# os32_master.net
KiCad netlist of a schematic drawn in EAGLE
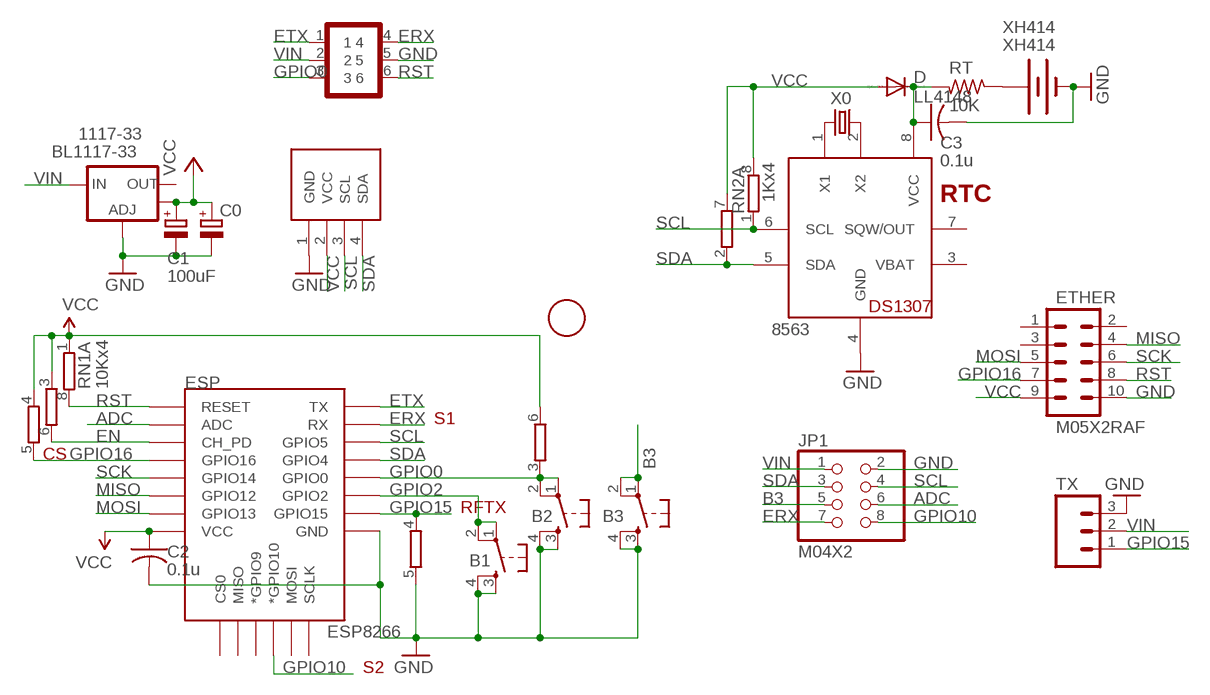
[diagram p0: schematic, sheet 1]

(export (version "E")
  (design (tool "Eeschema 10.0.6"))
  (components
    (comp (ref "1F")
      (value "FIDUCIAL")
      (footprint "eagle-import:FIDUCIAL_1MM")
      (libsource (lib "eagle-import") (part "FIDUCIAL"))
    )
    (comp (ref "1117-33")
      (value "BL1117-33")
      (footprint "eagle-import:SOT223")
      (libsource (lib "eagle-import") (part "V_REG_LM1117SOT223"))
    )
    (comp (ref "8563")
      (value "PCF8563")
      (footprint "eagle-import:SO08")
      (libsource (lib "eagle-import") (part "DS1307SOIC"))
    )
    (comp (ref "B1")
      (value "SPST_TACTEVQQ2")
      (footprint "eagle-import:EVQ-Q2")
      (libsource (lib "eagle-import") (part "SPST_TACTEVQQ2"))
    )
    (comp (ref "B2")
      (value "SPST_TACTEVQQ2")
      (footprint "eagle-import:EVQ-Q2")
      (libsource (lib "eagle-import") (part "SPST_TACTEVQQ2"))
    )
    (comp (ref "B3")
      (value "SPST_TACTEVQQ2")
      (footprint "eagle-import:EVQ-Q2")
      (libsource (lib "eagle-import") (part "SPST_TACTEVQQ2"))
    )
    (comp (ref "C0")
      (value "CPOL-EUE2.5-5")
      (footprint "eagle-import:E2,5-5")
      (libsource (lib "eagle-import") (part "CPOL-EUE2.5-5"))
    )
    (comp (ref "C1")
      (value "100uF")
      (footprint "eagle-import:CT3528")
      (libsource (lib "eagle-import") (part "resistor_CPOL-EUCT3528"))
    )
    (comp (ref "C2")
      (value "0.1u")
      (footprint "eagle-import:C0603")
      (libsource (lib "eagle-import") (part "C-USC0603"))
    )
    (comp (ref "C3")
      (value "0.1u")
      (footprint "eagle-import:C0603")
      (libsource (lib "eagle-import") (part "C-USC0603"))
    )
    (comp (ref "D")
      (value "LL4148")
      (footprint "eagle-import:MINIMELF")
      (libsource (lib "eagle-import") (part "DIODE-MINIMELF"))
    )
    (comp (ref "ESP")
      (value "ESP8266")
      (footprint "eagle-import:ESP12E-SMD")
      (libsource (lib "eagle-import") (part "ESP12ESMD"))
    )
    (comp (ref "ETHER")
      (value "M05X2RAF")
      (footprint "eagle-import:2X5-RAF")
      (libsource (lib "eagle-import") (part "M05X2RAF"))
    )
    (comp (ref "JP1")
      (value "M04X2")
      (footprint "eagle-import:2X04")
      (libsource (lib "eagle-import") (part "PINHD-2X4"))
    )
    (comp (ref "LCD")
      (value "SSD1306_OLED_I2CSMD3")
      (footprint "eagle-import:SSD1306_OLED_I2C_SMD3")
      (libsource (lib "eagle-import") (part "SSD1306_OLED_I2CSMD3"))
    )
    (comp (ref "RN1")
      (value "10Kx4")
      (footprint "eagle-import:EXB38V")
      (libsource (lib "eagle-import") (part "4R-NEXB38V"))
    )
    (comp (ref "RN2")
      (value "1Kx4")
      (footprint "eagle-import:EXB38V")
      (libsource (lib "eagle-import") (part "4R-NEXB38V"))
    )
    (comp (ref "RT")
      (value "10K")
      (footprint "eagle-import:R0603")
      (libsource (lib "eagle-import") (part "R-US_R0603"))
    )
    (comp (ref "TX")
      (value "M03LOCK")
      (footprint "eagle-import:1X03_LOCK")
      (libsource (lib "eagle-import") (part "M03LOCK"))
    )
    (comp (ref "U$3")
      (value "GOLDFINGER_2X3")
      (footprint "eagle-import:GOLDFINGER_2X3")
      (libsource (lib "eagle-import") (part "GOLDFINGER_2X3"))
    )
    (comp (ref "X0")
      (value "32.768kHz")
      (footprint "eagle-import:MM20SS1")
      (libsource (lib "eagle-import") (part "CRYSTALMM20SS1"))
    )
    (comp (ref "XH414")
      (value "XH414")
      (footprint "eagle-import:BATTCON_XH414")
      (libsource (lib "eagle-import") (part "BATTERYXH414"))
    )
  )
  (nets
    (net (code "1") (name "/ADC") (class "Default")
      (node (ref "ESP") (pin "ADC") (pinfunction "ADC_ADC") (pintype "bidirectional"))
      (node (ref "JP1") (pin "6") (pinfunction "6_6") (pintype "passive"))
    )
    (net (code "2") (name "/B3") (class "Default")
      (node (ref "B3") (pin "1") (pinfunction "1_1") (pintype "passive"))
      (node (ref "B3") (pin "2") (pinfunction "2_2") (pintype "passive"))
      (node (ref "JP1") (pin "5") (pinfunction "5_5") (pintype "passive"))
    )
    (net (code "3") (name "/EN") (class "Default")
      (node (ref "ESP") (pin "CH_PD") (pinfunction "CH_PD_CH_PD") (pintype "bidirectional"))
      (node (ref "RN1") (pin "6") (pinfunction "2_6") (pintype "passive"))
    )
    (net (code "4") (name "/ERX") (class "Default")
      (node (ref "ESP") (pin "RXD0") (pinfunction "RX_RXD0") (pintype "bidirectional"))
      (node (ref "JP1") (pin "7") (pinfunction "7_7") (pintype "passive"))
      (node (ref "U$3") (pin "4") (pinfunction "4_4") (pintype "bidirectional"))
    )
    (net (code "5") (name "/ETX") (class "Default")
      (node (ref "ESP") (pin "TXD0") (pinfunction "TX_TXD0") (pintype "bidirectional"))
      (node (ref "U$3") (pin "1") (pinfunction "1_1") (pintype "bidirectional"))
    )
    (net (code "6") (name "/GPIO0") (class "Default")
      (node (ref "B2") (pin "1") (pinfunction "1_1") (pintype "passive"))
      (node (ref "B2") (pin "2") (pinfunction "2_2") (pintype "passive"))
      (node (ref "ESP") (pin "GPIO0") (pinfunction "GPIO0_GPIO0") (pintype "bidirectional"))
      (node (ref "RN2") (pin "3") (pinfunction "1_3") (pintype "passive"))
      (node (ref "U$3") (pin "3") (pinfunction "3_3") (pintype "bidirectional"))
    )
    (net (code "7") (name "/GPIO2") (class "Default")
      (node (ref "B1") (pin "1") (pinfunction "1_1") (pintype "passive"))
      (node (ref "B1") (pin "2") (pinfunction "2_2") (pintype "passive"))
      (node (ref "ESP") (pin "GPIO2") (pinfunction "GPIO2_GPIO2") (pintype "bidirectional"))
    )
    (net (code "8") (name "/GPIO10") (class "Default")
      (node (ref "ESP") (pin "GPIO10") (pinfunction "*GPIO10_GPIO10") (pintype "bidirectional"))
      (node (ref "JP1") (pin "8") (pinfunction "8_8") (pintype "passive"))
    )
    (net (code "9") (name "/GPIO15") (class "Default")
      (node (ref "ESP") (pin "GPIO15") (pinfunction "GPIO15_GPIO15") (pintype "bidirectional"))
      (node (ref "RN2") (pin "4") (pinfunction "1_4") (pintype "passive"))
      (node (ref "TX") (pin "1") (pinfunction "1_1") (pintype "passive"))
    )
    (net (code "10") (name "/GPIO16") (class "Default")
      (node (ref "ESP") (pin "GPIO16") (pinfunction "GPIO16_GPIO16") (pintype "bidirectional"))
      (node (ref "ETHER") (pin "7") (pinfunction "7_7") (pintype "passive"))
      (node (ref "RN1") (pin "5") (pinfunction "2_5") (pintype "passive"))
    )
    (net (code "11") (name "/MISO") (class "Default")
      (node (ref "ESP") (pin "GPIO12") (pinfunction "GPIO12_GPIO12") (pintype "bidirectional"))
      (node (ref "ETHER") (pin "4") (pinfunction "4_4") (pintype "passive"))
    )
    (net (code "12") (name "/MOSI") (class "Default")
      (node (ref "ESP") (pin "GPIO13") (pinfunction "GPIO13_GPIO13") (pintype "bidirectional"))
      (node (ref "ETHER") (pin "5") (pinfunction "5_5") (pintype "passive"))
    )
    (net (code "13") (name "/RST") (class "Default")
      (node (ref "ESP") (pin "RESET") (pinfunction "RESET_RESET") (pintype "bidirectional"))
      (node (ref "ETHER") (pin "8") (pinfunction "8_8") (pintype "passive"))
      (node (ref "RN1") (pin "8") (pinfunction "2_8") (pintype "passive"))
      (node (ref "U$3") (pin "6") (pinfunction "6_6") (pintype "bidirectional"))
    )
    (net (code "14") (name "/SCK") (class "Default")
      (node (ref "ESP") (pin "GPIO14") (pinfunction "GPIO14_GPIO14") (pintype "bidirectional"))
      (node (ref "ETHER") (pin "6") (pinfunction "6_6") (pintype "passive"))
    )
    (net (code "15") (name "/SCL") (class "Default")
      (node (ref "8563") (pin "6") (pinfunction "SCL_6") (pintype "bidirectional"))
      (node (ref "ESP") (pin "GPIO5") (pinfunction "GPIO5_GPIO5") (pintype "bidirectional"))
      (node (ref "JP1") (pin "4") (pinfunction "4_4") (pintype "passive"))
      (node (ref "LCD") (pin "3") (pinfunction "SCL_3") (pintype "bidirectional"))
      (node (ref "RN2") (pin "1") (pinfunction "1_1") (pintype "passive"))
    )
    (net (code "16") (name "/SDA") (class "Default")
      (node (ref "8563") (pin "5") (pinfunction "SDA_5") (pintype "bidirectional"))
      (node (ref "ESP") (pin "GPIO4") (pinfunction "GPIO4_GPIO4") (pintype "bidirectional"))
      (node (ref "JP1") (pin "3") (pinfunction "3_3") (pintype "passive"))
      (node (ref "LCD") (pin "4") (pinfunction "SDA_4") (pintype "bidirectional"))
      (node (ref "RN2") (pin "2") (pinfunction "1_2") (pintype "passive"))
    )
    (net (code "17") (name "/VBAT") (class "Default")
      (node (ref "8563") (pin "3") (pinfunction "VBAT_3") (pintype "power_in"))
    )
    (net (code "18") (name "/VIN") (class "Default")
      (node (ref "1117-33") (pin "3") (pinfunction "IN_3") (pintype "input"))
      (node (ref "JP1") (pin "1") (pinfunction "1_1") (pintype "passive"))
      (node (ref "TX") (pin "2") (pinfunction "2_2") (pintype "passive"))
      (node (ref "U$3") (pin "2") (pinfunction "2_2") (pintype "bidirectional"))
    )
    (net (code "19") (name "GND") (class "Default")
      (node (ref "1117-33") (pin "1") (pinfunction "ADJ_1") (pintype "input"))
      (node (ref "8563") (pin "4") (pinfunction "GND_4") (pintype "power_in"))
      (node (ref "B1") (pin "3") (pinfunction "3_3") (pintype "passive"))
      (node (ref "B1") (pin "4") (pinfunction "4_4") (pintype "passive"))
      (node (ref "B2") (pin "3") (pinfunction "3_3") (pintype "passive"))
      (node (ref "B2") (pin "4") (pinfunction "4_4") (pintype "passive"))
      (node (ref "B3") (pin "3") (pinfunction "3_3") (pintype "passive"))
      (node (ref "B3") (pin "4") (pinfunction "4_4") (pintype "passive"))
      (node (ref "C0") (pin "-") (pinfunction "-_-") (pintype "passive"))
      (node (ref "C1") (pin "+") (pinfunction "-_+") (pintype "passive"))
      (node (ref "C2") (pin "2") (pinfunction "2_2") (pintype "passive"))
      (node (ref "C3") (pin "2") (pinfunction "2_2") (pintype "passive"))
      (node (ref "ESP") (pin "GND") (pinfunction "GND_GND") (pintype "bidirectional"))
      (node (ref "ETHER") (pin "10") (pinfunction "10_10") (pintype "passive"))
      (node (ref "JP1") (pin "2") (pinfunction "2_2") (pintype "passive"))
      (node (ref "LCD") (pin "1") (pinfunction "GND_1") (pintype "power_in"))
      (node (ref "RN2") (pin "5") (pinfunction "2_5") (pintype "passive"))
      (node (ref "TX") (pin "3") (pinfunction "3_3") (pintype "passive"))
      (node (ref "U$3") (pin "5") (pinfunction "5_5") (pintype "bidirectional"))
      (node (ref "XH414") (pin "P$1") (pinfunction "-_P$1") (pintype "power_in"))
    )
    (net (code "20") (name "Net-(8563-VCC)") (class "Default")
      (node (ref "8563") (pin "8") (pinfunction "VCC_8") (pintype "power_in"))
      (node (ref "C3") (pin "1") (pinfunction "1_1") (pintype "passive"))
      (node (ref "D") (pin "C") (pinfunction "C_C") (pintype "passive"))
      (node (ref "RT") (pin "2") (pinfunction "2_2") (pintype "passive"))
    )
    (net (code "21") (name "Net-(8563-X1)") (class "Default")
      (node (ref "8563") (pin "1") (pinfunction "X1_1") (pintype "passive"))
      (node (ref "X0") (pin "1") (pinfunction "1_1") (pintype "passive"))
    )
    (net (code "22") (name "Net-(8563-X2)") (class "Default")
      (node (ref "8563") (pin "2") (pinfunction "X2_2") (pintype "passive"))
      (node (ref "X0") (pin "4") (pinfunction "2_4") (pintype "passive"))
    )
    (net (code "23") (name "Net-(XH414-+)") (class "Default")
      (node (ref "RT") (pin "1") (pinfunction "1_1") (pintype "passive"))
      (node (ref "XH414") (pin "P$2") (pinfunction "+_P$2") (pintype "power_in"))
    )
    (net (code "24") (name "VCC") (class "Default")
      (node (ref "1117-33") (pin "4") (pinfunction "OUT_4") (pintype "bidirectional"))
      (node (ref "C0") (pin "+") (pinfunction "+_+") (pintype "passive"))
      (node (ref "C1") (pin "-") (pinfunction "+_-") (pintype "passive"))
      (node (ref "C2") (pin "1") (pinfunction "1_1") (pintype "passive"))
      (node (ref "D") (pin "A") (pinfunction "A_A") (pintype "passive"))
      (node (ref "ESP") (pin "VCC") (pinfunction "VCC_VCC") (pintype "bidirectional"))
      (node (ref "ETHER") (pin "9") (pinfunction "9_9") (pintype "passive"))
      (node (ref "LCD") (pin "2") (pinfunction "VCC_2") (pintype "power_in"))
      (node (ref "RN1") (pin "1") (pinfunction "1_1") (pintype "passive"))
      (node (ref "RN1") (pin "3") (pinfunction "1_3") (pintype "passive"))
      (node (ref "RN1") (pin "4") (pinfunction "1_4") (pintype "passive"))
      (node (ref "RN2") (pin "6") (pinfunction "2_6") (pintype "passive"))
      (node (ref "RN2") (pin "7") (pinfunction "2_7") (pintype "passive"))
      (node (ref "RN2") (pin "8") (pinfunction "2_8") (pintype "passive"))
    )
    (net (code "25") (name "unconnected-(1117-33-OUT-Pad2)") (class "Default")
      (node (ref "1117-33") (pin "2") (pinfunction "OUT_2") (pintype "bidirectional"))
    )
    (net (code "26") (name "unconnected-(8563-SQW{slash}OUT-Pad7)") (class "Default")
      (node (ref "8563") (pin "7") (pinfunction "SQW/OUT_7") (pintype "bidirectional"))
    )
    (net (code "27") (name "unconnected-(ESP-*GPIO9-PadGPIO9)") (class "Default")
      (node (ref "ESP") (pin "GPIO9") (pinfunction "*GPIO9_GPIO9") (pintype "bidirectional"))
    )
    (net (code "28") (name "unconnected-(ESP-PadCS0)") (class "Default")
      (node (ref "ESP") (pin "CS0") (pinfunction "CS0_CS0") (pintype "bidirectional"))
    )
    (net (code "29") (name "unconnected-(ESP-PadMISO)") (class "Default")
      (node (ref "ESP") (pin "MISO") (pinfunction "MISO_MISO") (pintype "bidirectional"))
    )
    (net (code "30") (name "unconnected-(ESP-PadMOSI)") (class "Default")
      (node (ref "ESP") (pin "MOSI") (pinfunction "MOSI_MOSI") (pintype "bidirectional"))
    )
    (net (code "31") (name "unconnected-(ESP-PadSCLK)") (class "Default")
      (node (ref "ESP") (pin "SCLK") (pinfunction "SCLK_SCLK") (pintype "bidirectional"))
    )
    (net (code "32") (name "unconnected-(ETHER-Pad1)") (class "Default")
      (node (ref "ETHER") (pin "1") (pinfunction "1_1") (pintype "passive"))
    )
    (net (code "33") (name "unconnected-(ETHER-Pad2)") (class "Default")
      (node (ref "ETHER") (pin "2") (pinfunction "2_2") (pintype "passive"))
    )
    (net (code "34") (name "unconnected-(ETHER-Pad3)") (class "Default")
      (node (ref "ETHER") (pin "3") (pinfunction "3_3") (pintype "passive"))
    )
  )
)
